# 3.net
KiCad netlist of a schematic drawn in Altium Designer
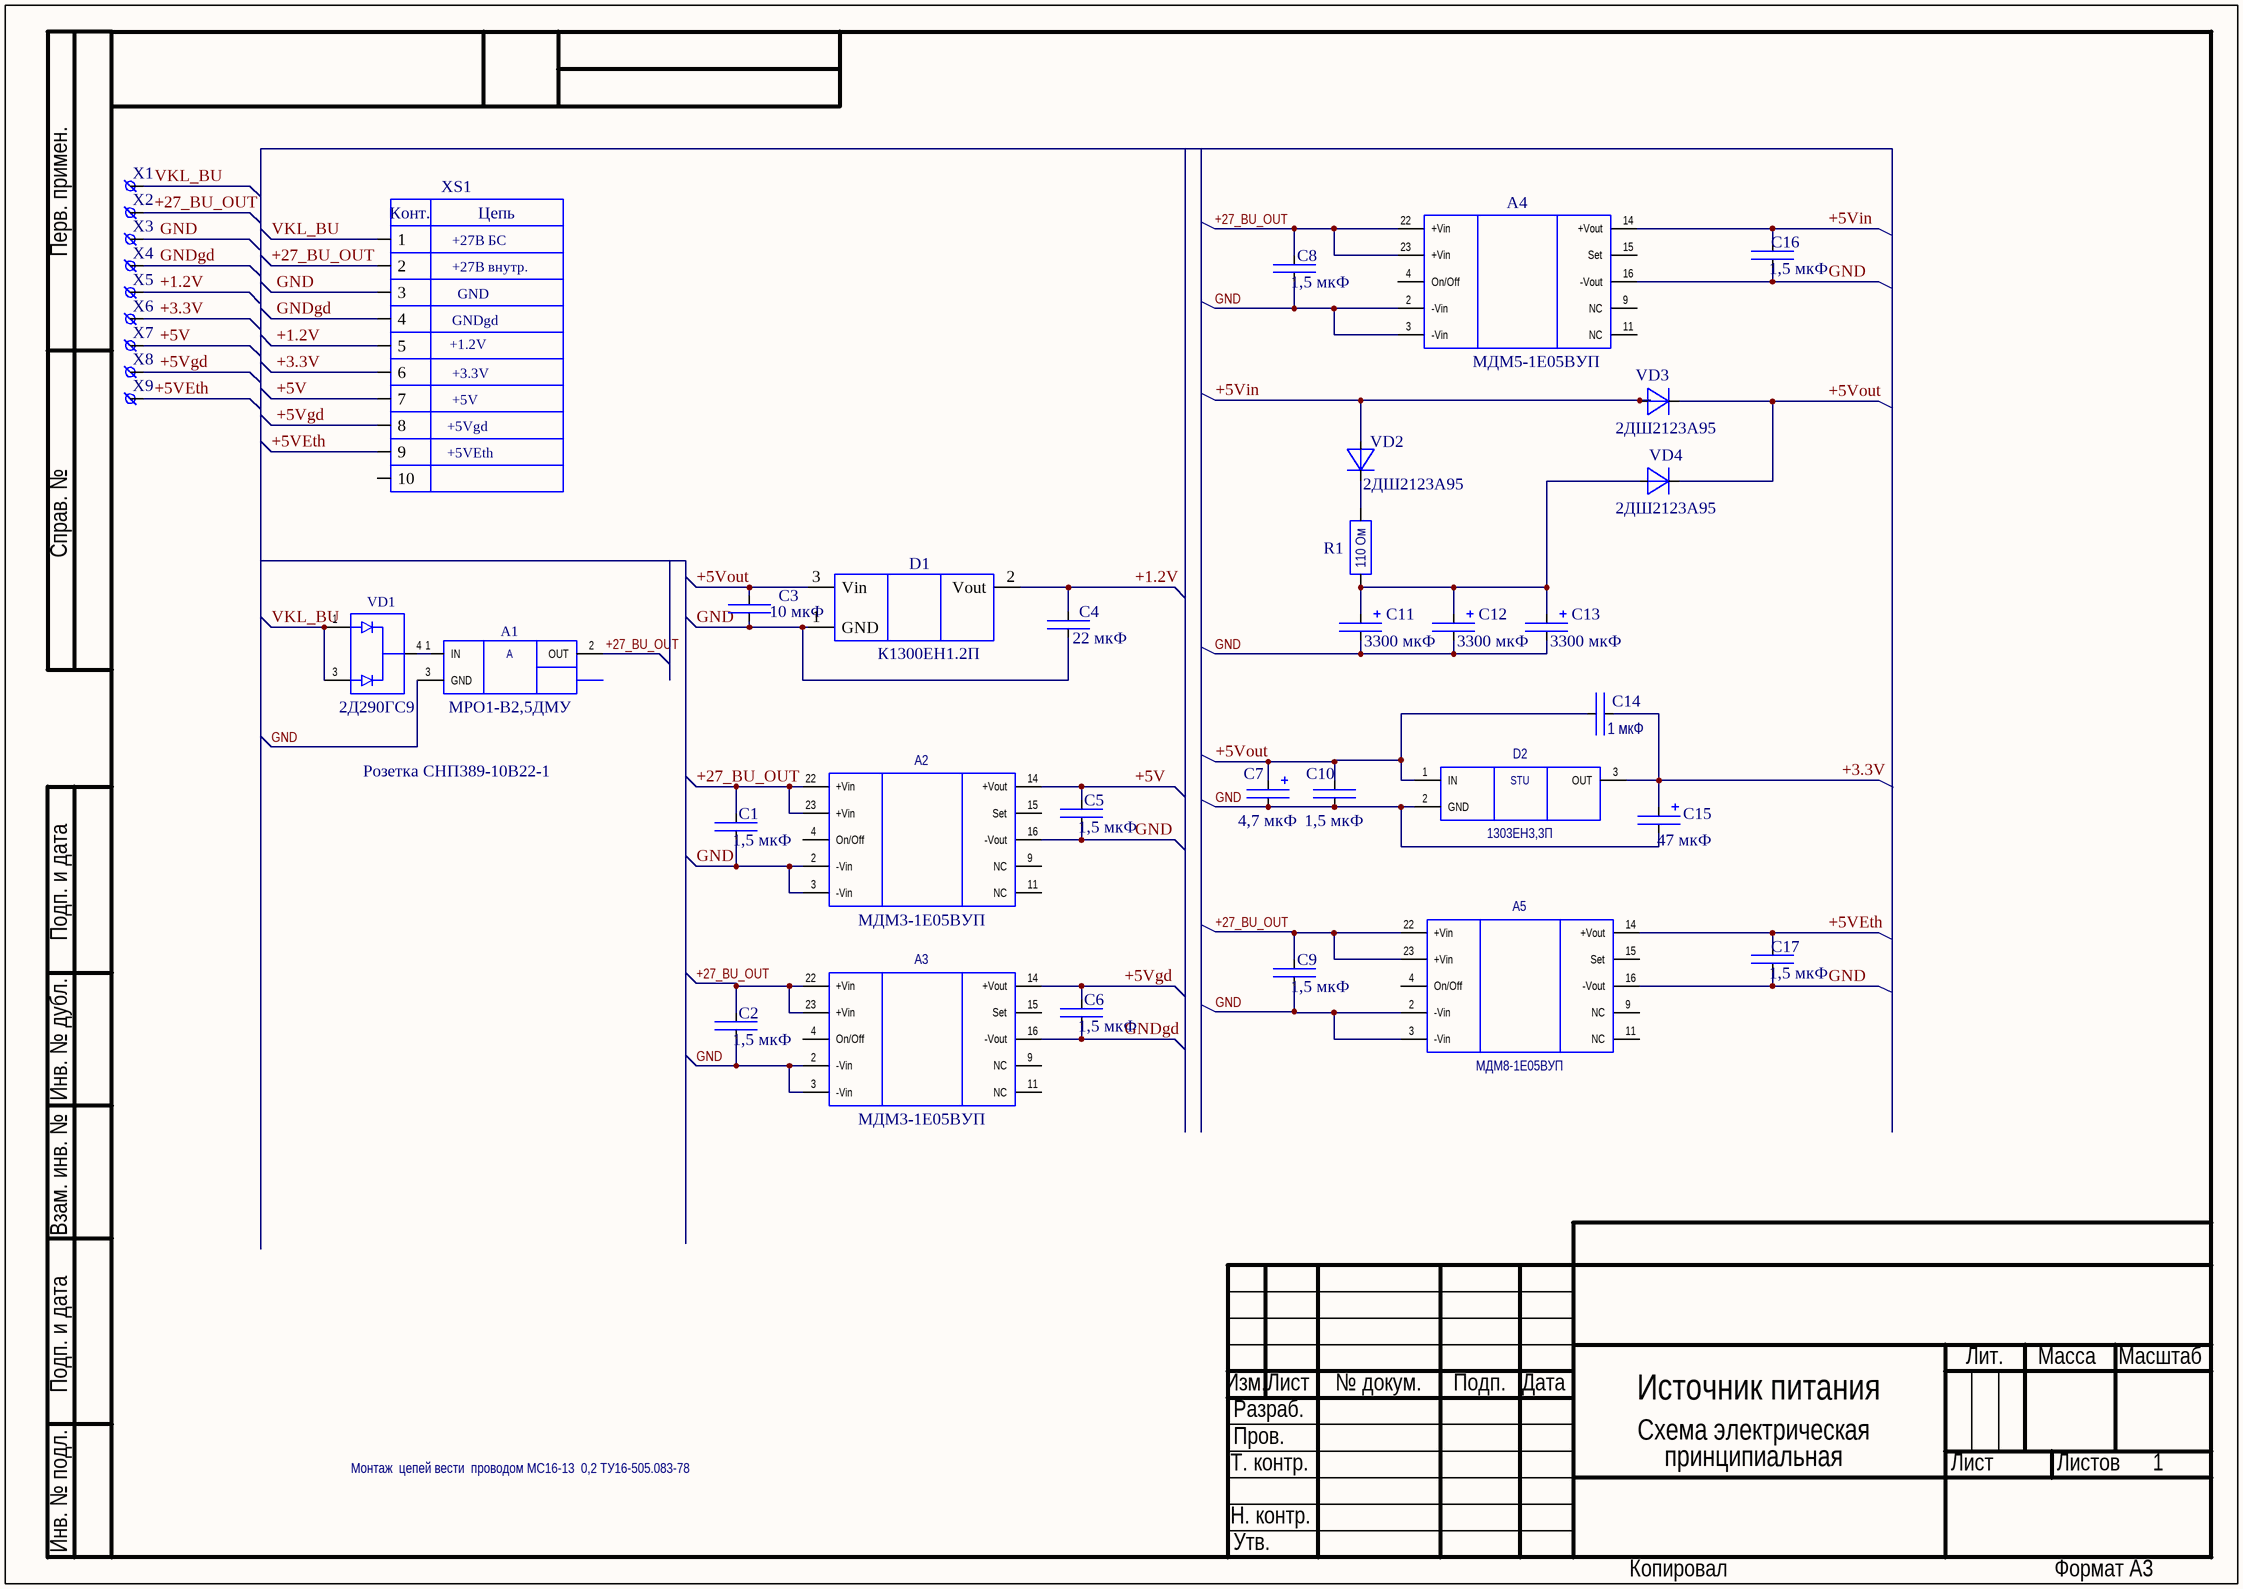
[diagram p0: Источник_питанияЭ3.SchDoc]

(export (version "E")
  (design (tool "Eeschema 10.0.6"))
  (components
    (comp (ref "A1")
      (value "МРО1-В2,5ДМУ")
      (footprint "МРО1-У - БЕЗ ОТВ")
      (description "Модуль защиты и фильтрации")
      (libsource (lib "ControlCPU") (part "МРО"))
    )
    (comp (ref "A2")
      (value "МДМ3-1Е05ВУП")
      (footprint "МДМ3-Е-У")
      (libsource (lib "SIK") (part "МДМ3-1Е3.3ВП"))
    )
    (comp (ref "A3")
      (value "МДМ3-1Е05ВУП")
      (footprint "МДМ3-Е-У")
      (libsource (lib "SIK") (part "МДМ3-1Е3.3ВП"))
    )
    (comp (ref "A4")
      (value "Модуль питания МДМ5-1Е05ВУП БКЮС.430609.002-01ТУ")
      (footprint "МДМ3-Е-У")
      (fields (field (name "PARTNUMBER") "МДМ5-1Е05ВУП"))
      (libsource (lib "SIK") (part "МДМ3-1Е3.3ВП"))
    )
    (comp (ref "A5")
      (value "МДМ8-1Е05ВУП")
      (footprint "МДМ8-Е-У_БКЮС.430609.002-01ТУ")
      (libsource (lib "SIK") (part "МДМ3-1Е3.3ВП"))
    )
    (comp (ref "C1")
      (value "1,5 мкФ")
      (footprint "K10-67_10x8x3.5")
      (description "Керамический чип-конденсатор серии К10-79")
      (fields (field (name "PARTNUMBER") "К10-67-Н50-100В-1,5 мкФ ±20% луженые"))
      (libsource (lib "SIK") (part "К10-69"))
    )
    (comp (ref "C2")
      (value "1,5 мкФ")
      (footprint "K10-67_10x8x3.5")
      (description "Керамический чип-конденсатор серии К10-79")
      (fields (field (name "PARTNUMBER") "К10-67-Н50-100В-1,5 мкФ ±20% луженые"))
      (libsource (lib "SIK") (part "К10-69"))
    )
    (comp (ref "C3")
      (value "10 мкФ")
      (description "Керамический чип-конденсатор серии К10-79")
      (fields (field (name "PARTNUMBER") "К10-69в-*-* В- * ± *% *"))
      (libsource (lib "ControlCPU") (part "К10-69"))
    )
    (comp (ref "C4")
      (value "22 мкФ")
      (description "Керамический чип-конденсатор серии К10-79")
      (fields (field (name "PARTNUMBER") "К10-69в-*-* В- * ± *% *"))
      (libsource (lib "ControlCPU") (part "К10-69"))
    )
    (comp (ref "C5")
      (value "1,5 мкФ")
      (footprint "K10-69B_4.5_3.2(1812)")
      (description "Керамический чип-конденсатор серии К10-79")
      (fields (field (name "PARTNUMBER") "К10-69в-Н90-25В-1,5 мкФ ±20% (4532М) луженые"))
      (libsource (lib "SIK") (part "К10-69"))
    )
    (comp (ref "C6")
      (value "1,5 мкФ")
      (footprint "K10-69B_4.5_3.2(1812)")
      (description "Керамический чип-конденсатор серии К10-79")
      (fields (field (name "PARTNUMBER") "К10-69в-Н90-25В-1,5 мкФ ±20% (4532М) луженые"))
      (libsource (lib "SIK") (part "К10-69"))
    )
    (comp (ref "C7")
      (value "4,7 мкФ")
      (footprint "TANTAL-A(3216)")
      (description "Оксидно-полупроводниковый танталовый чип-конденсатор серии К53-68")
      (fields (field (name "PARTNUMBER") "К53-68 \"A\" 10В-4,7 мкФ ±10%"))
      (libsource (lib "ControlBoard") (part "К53-67"))
    )
    (comp (ref "C8")
      (value "1,5 мкФ")
      (footprint "K10-67_10x8x3.5")
      (description "Керамический чип-конденсатор серии К10-79")
      (fields (field (name "PARTNUMBER") "К10-67-Н50-100В-1,5 мкФ ±20% луженые"))
      (libsource (lib "SIK") (part "К10-69"))
    )
    (comp (ref "C9")
      (value "1,5 мкФ")
      (footprint "K10-67_10x8x3.5")
      (description "Керамический чип-конденсатор серии К10-79")
      (fields (field (name "PARTNUMBER") "К10-67-Н50-100В-1,5 мкФ ±20% луженые"))
      (libsource (lib "SIK") (part "К10-69"))
    )
    (comp (ref "C10")
      (value "1,5 мкФ")
      (footprint "K10-69B_4.5_3.2(1812)")
      (description "Керамический чип-конденсатор серии К10-79")
      (fields (field (name "PARTNUMBER") "К10-69в-Н90-25В-1,5 мкФ ±20% (4532М) луженые"))
      (libsource (lib "ControlBoard") (part "К10-69"))
    )
    (comp (ref "C11")
      (value "3300 мкФ")
      (footprint "k52-18-16B-2200")
      (description "Оксидно-полупроводниковый танталовый чип-конденсатор серии К53-68")
      (fields (field (name "PARTNUMBER") "К52-18-10В-3300 мкФ ±20%"))
      (libsource (lib "SIK") (part "К53-67"))
    )
    (comp (ref "C12")
      (value "3300 мкФ")
      (footprint "k52-18-16B-2200")
      (description "Оксидно-полупроводниковый танталовый чип-конденсатор серии К53-68")
      (fields (field (name "PARTNUMBER") "К52-18-10В-3300 мкФ ±20%"))
      (libsource (lib "SIK") (part "К53-67"))
    )
    (comp (ref "C13")
      (value "3300 мкФ")
      (footprint "k52-18-16B-2200")
      (description "Оксидно-полупроводниковый танталовый чип-конденсатор серии К53-68")
      (fields (field (name "PARTNUMBER") "К52-18-10В-3300 мкФ ±20%"))
      (libsource (lib "SIK") (part "К53-67"))
    )
    (comp (ref "C14")
      (value "1 мкФ")
      (footprint "K10-69B_4.5_3.2(1812)")
      (description "Керамический чип-конденсатор серии К10-79")
      (fields (field (name "PARTNUMBER") "К10-69в-Н90-25В-1 мкФ ±20% (4532М луженые"))
      (libsource (lib "ControlBoard") (part "К10-69"))
    )
    (comp (ref "C15")
      (value "47 мкФ")
      (footprint "TANTAL-C(6032)")
      (description "Оксидно-полупроводниковый танталовый чип-конденсатор серии К53-68")
      (fields (field (name "PARTNUMBER") "К53-68 \"C\" 10В-47 мкФ ±10%"))
      (libsource (lib "ControlBoard") (part "К53-67"))
    )
    (comp (ref "C16")
      (value "1,5 мкФ")
      (footprint "K10-69B_4.5_3.2(1812)")
      (description "Керамический чип-конденсатор серии К10-79")
      (fields (field (name "PARTNUMBER") "К10-69в-Н90-25В-1,5 мкФ ±20% (4532М) луженые"))
      (libsource (lib "SIK") (part "К10-69"))
    )
    (comp (ref "C17")
      (value "1,5 мкФ")
      (footprint "K10-69B_4.5_3.2(1812)")
      (description "Керамический чип-конденсатор серии К10-79")
      (fields (field (name "PARTNUMBER") "К10-69в-Н90-25В-1,5 мкФ ±20% (4532М) луженые"))
      (libsource (lib "SIK") (part "К10-69"))
    )
    (comp (ref "D1") (value "К1300ЕН1.2П") (libsource (lib "ControlCPU") (part "К1300ЕН1.2П")))
    (comp (ref "D2")
      (value "1303ЕН3,3П")
      (footprint "TO-220")
      (libsource (lib "ControlBoard") (part "1303ЕН3,3П"))
    )
    (comp (ref "R1")
      (value "110 Ом")
      (footprint "P1-12-1(2512)")
      (description "Постоянные непроволочные безвыводные резисторы общего применения Р1-12")
      (fields (field (name "PARTNUMBER") "Р1-12-1-110 Ом±5 %-T"))
      (libsource (lib "ControlCPU") (part "Р1-12"))
    )
    (comp (ref "VD1")
      (value "2Д290ГС9")
      (footprint "KT-89")
      (description "Диод 2Д290ГС9")
      (libsource (lib "SIK") (part "2Д290ГС9"))
    )
    (comp (ref "VD2")
      (value "2ДШ2123А95")
      (footprint "KT-99-1")
      (description "Диод Шоттки")
      (libsource (lib "ControlCPU") (part "2ДШ2123А95"))
    )
    (comp (ref "VD3")
      (value "2ДШ2123А95")
      (footprint "KT-99-1")
      (description "Диод Шоттки")
      (libsource (lib "ControlCPU") (part "2ДШ2123А95"))
    )
    (comp (ref "VD4")
      (value "2ДШ2123А95")
      (footprint "KT-99-1")
      (description "Диод Шоттки")
      (libsource (lib "ControlCPU") (part "2ДШ2123А95"))
    )
    (comp (ref "X1")
      (value "CONT")
      (footprint "Пл.площ.3х1.25")
      (description "CONT1_SMD")
      (fields (field (name "PARTNUMBER") "контактное поле"))
      (libsource (lib "ControlCPU") (part "CONT"))
    )
    (comp (ref "X2")
      (value "CONT")
      (footprint "Пл.площ.3х1.25")
      (description "CONT1_SMD")
      (fields (field (name "PARTNUMBER") "контактное поле"))
      (libsource (lib "ControlCPU") (part "CONT"))
    )
    (comp (ref "X3")
      (value "CONT")
      (footprint "Пл.площ.3х1.25")
      (description "CONT1_SMD")
      (fields (field (name "PARTNUMBER") "контактное поле"))
      (libsource (lib "ControlCPU") (part "CONT"))
    )
    (comp (ref "X4")
      (value "CONT")
      (footprint "Пл.площ.3х1.25")
      (description "CONT1_SMD")
      (fields (field (name "PARTNUMBER") "контактное поле"))
      (libsource (lib "ControlCPU") (part "CONT"))
    )
    (comp (ref "X5")
      (value "CONT")
      (footprint "Пл.площ.3х1.25")
      (description "CONT1_SMD")
      (fields (field (name "PARTNUMBER") "контактное поле"))
      (libsource (lib "ControlCPU") (part "CONT"))
    )
    (comp (ref "X6")
      (value "CONT")
      (footprint "Пл.площ.3х1.25")
      (description "CONT1_SMD")
      (fields (field (name "PARTNUMBER") "контактное поле"))
      (libsource (lib "ControlCPU") (part "CONT"))
    )
    (comp (ref "X7")
      (value "CONT")
      (footprint "Пл.площ.3х1.25")
      (description "CONT1_SMD")
      (fields (field (name "PARTNUMBER") "контактное поле"))
      (libsource (lib "ControlCPU") (part "CONT"))
    )
    (comp (ref "X8")
      (value "CONT")
      (footprint "Пл.площ.3х1.25")
      (description "CONT1_SMD")
      (fields (field (name "PARTNUMBER") "контактное поле"))
      (libsource (lib "ControlCPU") (part "CONT"))
    )
    (comp (ref "X9")
      (value "CONT")
      (footprint "Пл.площ.3х1.25")
      (description "CONT1_SMD")
      (fields (field (name "PARTNUMBER") "контактное поле"))
      (libsource (lib "ControlCPU") (part "CONT"))
    )
    (comp (ref "XS1")
      (value "Розетка СНП389-10В22-1")
      (description "Розетка 10 контактов")
      (libsource (lib "ControlCPU") (part "10-Pin"))
    )
  )
  (nets
    (net (code "1") (name "/+1.2V") (class "Default")
      (node (ref "C4") (pin "1") (pinfunction "1_1") (pintype "passive"))
      (node (ref "D1") (pin "2") (pinfunction "Vout_2") (pintype "passive"))
      (node (ref "X5") (pin "1") (pinfunction "1_1") (pintype "passive"))
      (node (ref "XS1") (pin "5") (pinfunction "5_5") (pintype "passive"))
    )
    (net (code "2") (name "/+3.3V") (class "Default")
      (node (ref "C14") (pin "1") (pinfunction "1_1") (pintype "passive"))
      (node (ref "C15") (pin "1") (pinfunction "1_1") (pintype "passive"))
      (node (ref "D2") (pin "3") (pinfunction "OUT_3") (pintype "passive"))
      (node (ref "X6") (pin "1") (pinfunction "1_1") (pintype "passive"))
      (node (ref "XS1") (pin "6") (pinfunction "6_6") (pintype "passive"))
    )
    (net (code "3") (name "/+5V") (class "Default")
      (node (ref "A2") (pin "14") (pinfunction "+Vout_14") (pintype "passive"))
      (node (ref "C5") (pin "1") (pinfunction "1_1") (pintype "passive"))
      (node (ref "X7") (pin "1") (pinfunction "1_1") (pintype "passive"))
      (node (ref "XS1") (pin "7") (pinfunction "7_7") (pintype "passive"))
    )
    (net (code "4") (name "/+5VEth") (class "Default")
      (node (ref "A5") (pin "14") (pinfunction "+Vout_14") (pintype "passive"))
      (node (ref "C17") (pin "1") (pinfunction "1_1") (pintype "passive"))
      (node (ref "X9") (pin "1") (pinfunction "1_1") (pintype "passive"))
      (node (ref "XS1") (pin "9") (pinfunction "9_9") (pintype "passive"))
    )
    (net (code "5") (name "/+5Vgd") (class "Default")
      (node (ref "A3") (pin "14") (pinfunction "+Vout_14") (pintype "passive"))
      (node (ref "C6") (pin "1") (pinfunction "1_1") (pintype "passive"))
      (node (ref "X8") (pin "1") (pinfunction "1_1") (pintype "passive"))
      (node (ref "XS1") (pin "8") (pinfunction "8_8") (pintype "passive"))
    )
    (net (code "6") (name "/+5Vin") (class "Default")
      (node (ref "A4") (pin "14") (pinfunction "+Vout_14") (pintype "passive"))
      (node (ref "C16") (pin "1") (pinfunction "1_1") (pintype "passive"))
      (node (ref "VD2") (pin "2") (pintype "passive"))
      (node (ref "VD3") (pin "2") (pintype "passive"))
    )
    (net (code "7") (name "/+5Vout") (class "Default")
      (node (ref "C10") (pin "2") (pinfunction "2_2") (pintype "passive"))
      (node (ref "C14") (pin "2") (pinfunction "2_2") (pintype "passive"))
      (node (ref "C3") (pin "1") (pinfunction "1_1") (pintype "passive"))
      (node (ref "C7") (pin "1") (pinfunction "1_1") (pintype "passive"))
      (node (ref "D1") (pin "3") (pinfunction "Vin_3") (pintype "passive"))
      (node (ref "D2") (pin "1") (pinfunction "IN_1") (pintype "passive"))
      (node (ref "VD3") (pin "3") (pintype "passive"))
      (node (ref "VD4") (pin "3") (pintype "passive"))
    )
    (net (code "8") (name "/+27_BU_OUT") (class "Default")
      (node (ref "A1") (pin "2") (pinfunction "OUT_2") (pintype "passive"))
      (node (ref "A2") (pin "22") (pinfunction "+Vin_22") (pintype "passive"))
      (node (ref "A2") (pin "23") (pinfunction "+Vin_23") (pintype "passive"))
      (node (ref "A3") (pin "22") (pinfunction "+Vin_22") (pintype "passive"))
      (node (ref "A3") (pin "23") (pinfunction "+Vin_23") (pintype "passive"))
      (node (ref "A4") (pin "22") (pinfunction "+Vin_22") (pintype "passive"))
      (node (ref "A4") (pin "23") (pinfunction "+Vin_23") (pintype "passive"))
      (node (ref "A5") (pin "22") (pinfunction "+Vin_22") (pintype "passive"))
      (node (ref "A5") (pin "23") (pinfunction "+Vin_23") (pintype "passive"))
      (node (ref "C1") (pin "1") (pinfunction "1_1") (pintype "passive"))
      (node (ref "C2") (pin "1") (pinfunction "1_1") (pintype "passive"))
      (node (ref "C8") (pin "1") (pinfunction "1_1") (pintype "passive"))
      (node (ref "C9") (pin "1") (pinfunction "1_1") (pintype "passive"))
      (node (ref "X2") (pin "1") (pinfunction "1_1") (pintype "passive"))
      (node (ref "XS1") (pin "2") (pinfunction "2_2") (pintype "passive"))
    )
    (net (code "9") (name "/GND") (class "Default")
      (node (ref "A1") (pin "3") (pinfunction "GND_3") (pintype "passive"))
      (node (ref "A2") (pin "16") (pinfunction "-Vout_16") (pintype "passive"))
      (node (ref "A2") (pin "2") (pinfunction "-Vin_2") (pintype "passive"))
      (node (ref "A2") (pin "3") (pinfunction "-Vin_3") (pintype "passive"))
      (node (ref "A3") (pin "2") (pinfunction "-Vin_2") (pintype "passive"))
      (node (ref "A3") (pin "3") (pinfunction "-Vin_3") (pintype "passive"))
      (node (ref "A4") (pin "16") (pinfunction "-Vout_16") (pintype "passive"))
      (node (ref "A4") (pin "2") (pinfunction "-Vin_2") (pintype "passive"))
      (node (ref "A4") (pin "3") (pinfunction "-Vin_3") (pintype "passive"))
      (node (ref "A5") (pin "16") (pinfunction "-Vout_16") (pintype "passive"))
      (node (ref "A5") (pin "2") (pinfunction "-Vin_2") (pintype "passive"))
      (node (ref "A5") (pin "3") (pinfunction "-Vin_3") (pintype "passive"))
      (node (ref "C1") (pin "2") (pinfunction "2_2") (pintype "passive"))
      (node (ref "C10") (pin "1") (pinfunction "1_1") (pintype "passive"))
      (node (ref "C11") (pin "2") (pinfunction "2_2") (pintype "passive"))
      (node (ref "C12") (pin "2") (pinfunction "2_2") (pintype "passive"))
      (node (ref "C13") (pin "2") (pinfunction "2_2") (pintype "passive"))
      (node (ref "C15") (pin "2") (pinfunction "2_2") (pintype "passive"))
      (node (ref "C16") (pin "2") (pinfunction "2_2") (pintype "passive"))
      (node (ref "C17") (pin "2") (pinfunction "2_2") (pintype "passive"))
      (node (ref "C2") (pin "2") (pinfunction "2_2") (pintype "passive"))
      (node (ref "C3") (pin "2") (pinfunction "2_2") (pintype "passive"))
      (node (ref "C4") (pin "2") (pinfunction "2_2") (pintype "passive"))
      (node (ref "C5") (pin "2") (pinfunction "2_2") (pintype "passive"))
      (node (ref "C7") (pin "2") (pinfunction "2_2") (pintype "passive"))
      (node (ref "C8") (pin "2") (pinfunction "2_2") (pintype "passive"))
      (node (ref "C9") (pin "2") (pinfunction "2_2") (pintype "passive"))
      (node (ref "D1") (pin "1") (pinfunction "GND_1") (pintype "passive"))
      (node (ref "D2") (pin "2") (pinfunction "GND_2") (pintype "passive"))
      (node (ref "X3") (pin "1") (pinfunction "1_1") (pintype "passive"))
      (node (ref "XS1") (pin "3") (pinfunction "3_3") (pintype "passive"))
    )
    (net (code "10") (name "/GNDgd") (class "Default")
      (node (ref "A3") (pin "16") (pinfunction "-Vout_16") (pintype "passive"))
      (node (ref "C6") (pin "2") (pinfunction "2_2") (pintype "passive"))
      (node (ref "X4") (pin "1") (pinfunction "1_1") (pintype "passive"))
      (node (ref "XS1") (pin "4") (pinfunction "4_4") (pintype "passive"))
    )
    (net (code "11") (name "/VKL_BU") (class "Default")
      (node (ref "VD1") (pin "1") (pintype "passive"))
      (node (ref "VD1") (pin "3") (pintype "passive"))
      (node (ref "X1") (pin "1") (pinfunction "1_1") (pintype "passive"))
      (node (ref "XS1") (pin "1") (pinfunction "1_1") (pintype "passive"))
    )
    (net (code "12") (name "Net-(A1-IN)") (class "Default")
      (node (ref "A1") (pin "1") (pinfunction "IN_1") (pintype "passive"))
      (node (ref "VD1") (pin "4") (pintype "passive"))
    )
    (net (code "13") (name "Net-(C11-Pad1)") (class "Default")
      (node (ref "C11") (pin "1") (pinfunction "1_1") (pintype "passive"))
      (node (ref "C12") (pin "1") (pinfunction "1_1") (pintype "passive"))
      (node (ref "C13") (pin "1") (pinfunction "1_1") (pintype "passive"))
      (node (ref "R1") (pin "1") (pinfunction "1_1") (pintype "passive"))
      (node (ref "VD4") (pin "2") (pintype "passive"))
    )
    (net (code "14") (name "Net-(R1-Pad2)") (class "Default")
      (node (ref "R1") (pin "2") (pinfunction "2_2") (pintype "passive"))
      (node (ref "VD2") (pin "3") (pintype "passive"))
    )
    (net (code "15") (name "unconnected-(A2-NC-Pad9)") (class "Default")
      (node (ref "A2") (pin "9") (pinfunction "NC_9") (pintype "passive"))
    )
    (net (code "16") (name "unconnected-(A2-NC-Pad11)") (class "Default")
      (node (ref "A2") (pin "11") (pinfunction "NC_11") (pintype "passive"))
    )
    (net (code "17") (name "unconnected-(A2-On{slash}Off-Pad4)") (class "Default")
      (node (ref "A2") (pin "4") (pinfunction "On/Off_4") (pintype "passive"))
    )
    (net (code "18") (name "unconnected-(A2-Set-Pad15)") (class "Default")
      (node (ref "A2") (pin "15") (pinfunction "Set_15") (pintype "passive"))
    )
    (net (code "19") (name "unconnected-(A3-NC-Pad9)") (class "Default")
      (node (ref "A3") (pin "9") (pinfunction "NC_9") (pintype "passive"))
    )
    (net (code "20") (name "unconnected-(A3-NC-Pad11)") (class "Default")
      (node (ref "A3") (pin "11") (pinfunction "NC_11") (pintype "passive"))
    )
    (net (code "21") (name "unconnected-(A3-On{slash}Off-Pad4)") (class "Default")
      (node (ref "A3") (pin "4") (pinfunction "On/Off_4") (pintype "passive"))
    )
    (net (code "22") (name "unconnected-(A3-Set-Pad15)") (class "Default")
      (node (ref "A3") (pin "15") (pinfunction "Set_15") (pintype "passive"))
    )
    (net (code "23") (name "unconnected-(A4-NC-Pad9)") (class "Default")
      (node (ref "A4") (pin "9") (pinfunction "NC_9") (pintype "passive"))
    )
    (net (code "24") (name "unconnected-(A4-NC-Pad11)") (class "Default")
      (node (ref "A4") (pin "11") (pinfunction "NC_11") (pintype "passive"))
    )
    (net (code "25") (name "unconnected-(A4-On{slash}Off-Pad4)") (class "Default")
      (node (ref "A4") (pin "4") (pinfunction "On/Off_4") (pintype "passive"))
    )
    (net (code "26") (name "unconnected-(A4-Set-Pad15)") (class "Default")
      (node (ref "A4") (pin "15") (pinfunction "Set_15") (pintype "passive"))
    )
    (net (code "27") (name "unconnected-(A5-NC-Pad9)") (class "Default")
      (node (ref "A5") (pin "9") (pinfunction "NC_9") (pintype "passive"))
    )
    (net (code "28") (name "unconnected-(A5-NC-Pad11)") (class "Default")
      (node (ref "A5") (pin "11") (pinfunction "NC_11") (pintype "passive"))
    )
    (net (code "29") (name "unconnected-(A5-On{slash}Off-Pad4)") (class "Default")
      (node (ref "A5") (pin "4") (pinfunction "On/Off_4") (pintype "passive"))
    )
    (net (code "30") (name "unconnected-(A5-Set-Pad15)") (class "Default")
      (node (ref "A5") (pin "15") (pinfunction "Set_15") (pintype "passive"))
    )
    (net (code "31") (name "unconnected-(XS1-Pad10)") (class "Default")
      (node (ref "XS1") (pin "10") (pinfunction "10_10") (pintype "passive"))
    )
  )
)
